# 6x24V_InjectorDrivers.net
KiCad netlist of a schematic drawn in Altium Designer
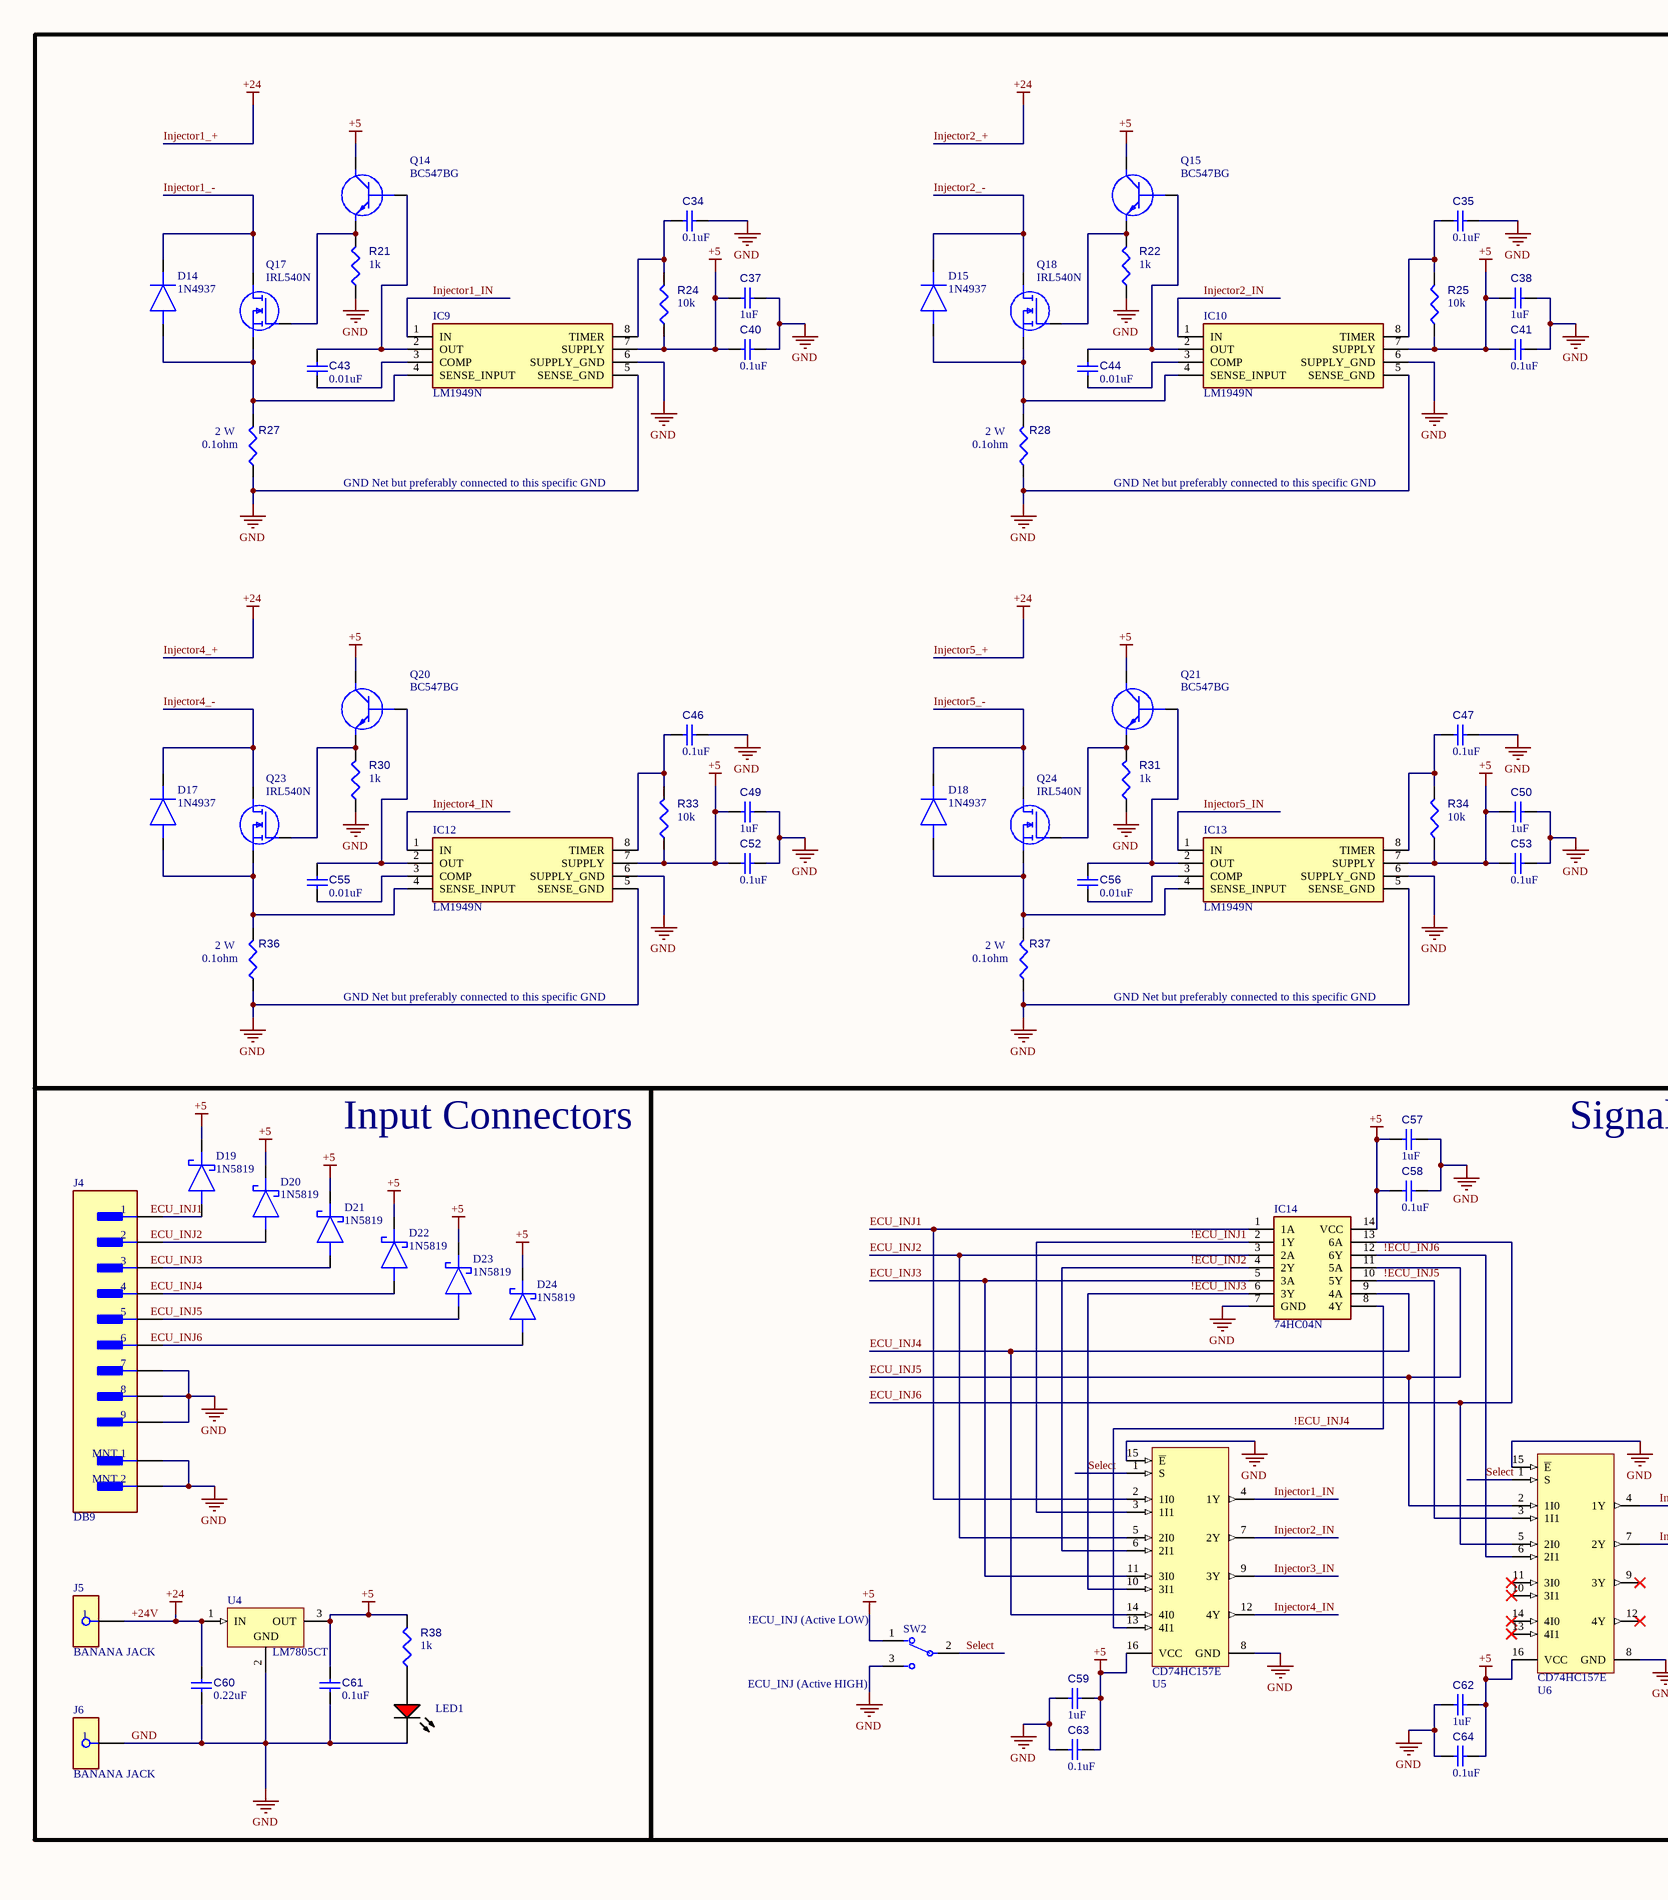
[diagram p0: 6x24V_InjectorDrivers.SchDoc, left]
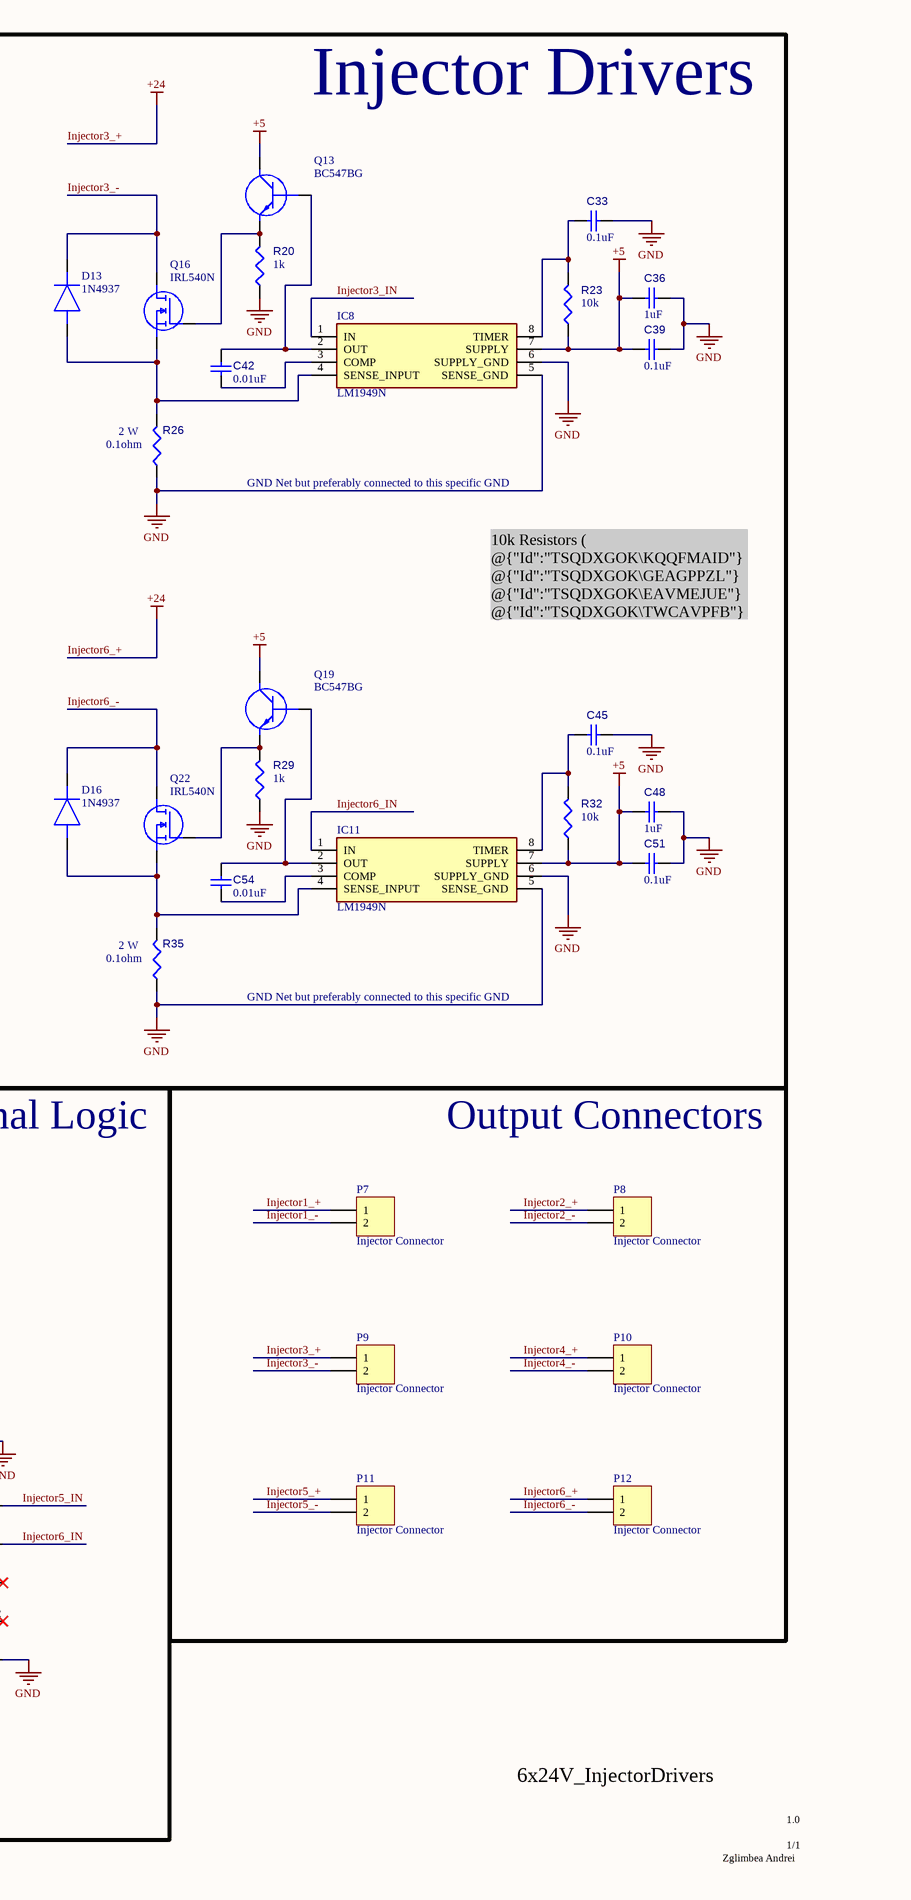
[diagram p1: 6x24V_InjectorDrivers.SchDoc, right]

(export (version "E")
  (design (tool "Eeschema 10.0.6"))
  (components
    (comp (ref "C33")
      (value "0.1uF")
      (footprint "CAPC0402(1005)60_L")
      (description "Chip Capacitor, 470nF +/-40%, 10V, 0402, Thickness 0.6 mm")
      (fields (field (name "TOLERANCE") "20%") (field (name "Comment") "100nF 12V"))
      (libsource (lib "Zglimbea Zglimbea") (part "CAP-NP-2"))
    )
    (comp (ref "C34")
      (value "0.1uF")
      (footprint "CAPC0402(1005)60_L")
      (description "Chip Capacitor, 470nF +/-40%, 10V, 0402, Thickness 0.6 mm")
      (fields (field (name "TOLERANCE") "20%") (field (name "Comment") "100nF 12V"))
      (libsource (lib "Zglimbea Zglimbea") (part "CAP-NP-2"))
    )
    (comp (ref "C35")
      (value "0.1uF")
      (footprint "CAPC0402(1005)60_L")
      (description "Chip Capacitor, 470nF +/-40%, 10V, 0402, Thickness 0.6 mm")
      (fields (field (name "TOLERANCE") "20%") (field (name "Comment") "100nF 12V"))
      (libsource (lib "Zglimbea Zglimbea") (part "CAP-NP-2"))
    )
    (comp (ref "C36")
      (value "1uF")
      (footprint "CAPC0402(1005)60_L")
      (description "Chip Capacitor, 470nF +/-40%, 10V, 0402, Thickness 0.6 mm")
      (fields (field (name "TOLERANCE") "20%") (field (name "Comment") "1uF 12V"))
      (libsource (lib "Zglimbea Zglimbea") (part "CAP-NP-2"))
    )
    (comp (ref "C37")
      (value "1uF")
      (footprint "CAPC0402(1005)60_L")
      (description "Chip Capacitor, 470nF +/-40%, 10V, 0402, Thickness 0.6 mm")
      (fields (field (name "TOLERANCE") "20%") (field (name "Comment") "1uF 12V"))
      (libsource (lib "Zglimbea Zglimbea") (part "CAP-NP-2"))
    )
    (comp (ref "C38")
      (value "1uF")
      (footprint "CAPC0402(1005)60_L")
      (description "Chip Capacitor, 470nF +/-40%, 10V, 0402, Thickness 0.6 mm")
      (fields (field (name "TOLERANCE") "20%") (field (name "Comment") "1uF 12V"))
      (libsource (lib "Zglimbea Zglimbea") (part "CAP-NP-2"))
    )
    (comp (ref "C39")
      (value "0.1uF")
      (footprint "CAPC0402(1005)60_L")
      (description "Chip Capacitor, 470nF +/-40%, 10V, 0402, Thickness 0.6 mm")
      (fields (field (name "TOLERANCE") "20%") (field (name "Comment") "100nF 12V"))
      (libsource (lib "Zglimbea Zglimbea") (part "CAP-NP-2"))
    )
    (comp (ref "C40")
      (value "0.1uF")
      (footprint "CAPC0402(1005)60_L")
      (description "Chip Capacitor, 470nF +/-40%, 10V, 0402, Thickness 0.6 mm")
      (fields (field (name "TOLERANCE") "20%") (field (name "Comment") "100nF 12V"))
      (libsource (lib "Zglimbea Zglimbea") (part "CAP-NP-2"))
    )
    (comp (ref "C41")
      (value "0.1uF")
      (footprint "CAPC0402(1005)60_L")
      (description "Chip Capacitor, 470nF +/-40%, 10V, 0402, Thickness 0.6 mm")
      (fields (field (name "TOLERANCE") "20%") (field (name "Comment") "100nF 12V"))
      (libsource (lib "Zglimbea Zglimbea") (part "CAP-NP-2"))
    )
    (comp (ref "C42")
      (value "0.01uF")
      (footprint "CAPC0402(1005)60_L")
      (description "Chip Capacitor, 470nF +/-40%, 10V, 0402, Thickness 0.6 mm")
      (fields (field (name "TOLERANCE") "20%") (field (name "Comment") "10nF 12V"))
      (libsource (lib "Zglimbea Zglimbea") (part "CAP-NP-2"))
    )
    (comp (ref "C43")
      (value "0.01uF")
      (footprint "CAPC0402(1005)60_L")
      (description "Chip Capacitor, 470nF +/-40%, 10V, 0402, Thickness 0.6 mm")
      (fields (field (name "TOLERANCE") "20%") (field (name "Comment") "10nF 12V"))
      (libsource (lib "Zglimbea Zglimbea") (part "CAP-NP-2"))
    )
    (comp (ref "C44")
      (value "0.01uF")
      (footprint "CAPC0402(1005)60_L")
      (description "Chip Capacitor, 470nF +/-40%, 10V, 0402, Thickness 0.6 mm")
      (fields (field (name "TOLERANCE") "20%") (field (name "Comment") "10nF 12V"))
      (libsource (lib "Zglimbea Zglimbea") (part "CAP-NP-2"))
    )
    (comp (ref "C45")
      (value "0.1uF")
      (footprint "CAPC0402(1005)60_L")
      (description "Chip Capacitor, 470nF +/-40%, 10V, 0402, Thickness 0.6 mm")
      (fields (field (name "TOLERANCE") "20%") (field (name "Comment") "100nF 12V"))
      (libsource (lib "Zglimbea Zglimbea") (part "CAP-NP-2"))
    )
    (comp (ref "C46")
      (value "0.1uF")
      (footprint "CAPC0402(1005)60_L")
      (description "Chip Capacitor, 470nF +/-40%, 10V, 0402, Thickness 0.6 mm")
      (fields (field (name "TOLERANCE") "20%") (field (name "Comment") "100nF 12V"))
      (libsource (lib "Zglimbea Zglimbea") (part "CAP-NP-2"))
    )
    (comp (ref "C47")
      (value "0.1uF")
      (footprint "CAPC0402(1005)60_L")
      (description "Chip Capacitor, 470nF +/-40%, 10V, 0402, Thickness 0.6 mm")
      (fields (field (name "TOLERANCE") "20%") (field (name "Comment") "100nF 12V"))
      (libsource (lib "Zglimbea Zglimbea") (part "CAP-NP-2"))
    )
    (comp (ref "C48")
      (value "1uF")
      (footprint "CAPC0402(1005)60_L")
      (description "Chip Capacitor, 470nF +/-40%, 10V, 0402, Thickness 0.6 mm")
      (fields (field (name "TOLERANCE") "20%") (field (name "Comment") "1uF 12V"))
      (libsource (lib "Zglimbea Zglimbea") (part "CAP-NP-2"))
    )
    (comp (ref "C49")
      (value "1uF")
      (footprint "CAPC0402(1005)60_L")
      (description "Chip Capacitor, 470nF +/-40%, 10V, 0402, Thickness 0.6 mm")
      (fields (field (name "TOLERANCE") "20%") (field (name "Comment") "1uF 12V"))
      (libsource (lib "Zglimbea Zglimbea") (part "CAP-NP-2"))
    )
    (comp (ref "C50")
      (value "1uF")
      (footprint "CAPC0402(1005)60_L")
      (description "Chip Capacitor, 470nF +/-40%, 10V, 0402, Thickness 0.6 mm")
      (fields (field (name "TOLERANCE") "20%") (field (name "Comment") "1uF 12V"))
      (libsource (lib "Zglimbea Zglimbea") (part "CAP-NP-2"))
    )
    (comp (ref "C51")
      (value "0.1uF")
      (footprint "CAPC0402(1005)60_L")
      (description "Chip Capacitor, 470nF +/-40%, 10V, 0402, Thickness 0.6 mm")
      (fields (field (name "TOLERANCE") "20%") (field (name "Comment") "100nF 12V"))
      (libsource (lib "Zglimbea Zglimbea") (part "CAP-NP-2"))
    )
    (comp (ref "C52")
      (value "0.1uF")
      (footprint "CAPC0402(1005)60_L")
      (description "Chip Capacitor, 470nF +/-40%, 10V, 0402, Thickness 0.6 mm")
      (fields (field (name "TOLERANCE") "20%") (field (name "Comment") "100nF 12V"))
      (libsource (lib "Zglimbea Zglimbea") (part "CAP-NP-2"))
    )
    (comp (ref "C53")
      (value "0.1uF")
      (footprint "CAPC0402(1005)60_L")
      (description "Chip Capacitor, 470nF +/-40%, 10V, 0402, Thickness 0.6 mm")
      (fields (field (name "TOLERANCE") "20%") (field (name "Comment") "100nF 12V"))
      (libsource (lib "Zglimbea Zglimbea") (part "CAP-NP-2"))
    )
    (comp (ref "C54")
      (value "0.01uF")
      (footprint "CAPC0402(1005)60_L")
      (description "Chip Capacitor, 470nF +/-40%, 10V, 0402, Thickness 0.6 mm")
      (fields (field (name "TOLERANCE") "20%") (field (name "Comment") "10nF 12V"))
      (libsource (lib "Zglimbea Zglimbea") (part "CAP-NP-2"))
    )
    (comp (ref "C55")
      (value "0.01uF")
      (footprint "CAPC0402(1005)60_L")
      (description "Chip Capacitor, 470nF +/-40%, 10V, 0402, Thickness 0.6 mm")
      (fields (field (name "TOLERANCE") "20%") (field (name "Comment") "10nF 12V"))
      (libsource (lib "Zglimbea Zglimbea") (part "CAP-NP-2"))
    )
    (comp (ref "C56")
      (value "0.01uF")
      (footprint "CAPC0402(1005)60_L")
      (description "Chip Capacitor, 470nF +/-40%, 10V, 0402, Thickness 0.6 mm")
      (fields (field (name "TOLERANCE") "20%") (field (name "Comment") "10nF 12V"))
      (libsource (lib "Zglimbea Zglimbea") (part "CAP-NP-2"))
    )
    (comp (ref "C57")
      (value "1uF")
      (footprint "CAPC0402(1005)60_L")
      (description "Chip Capacitor, 470nF +/-40%, 10V, 0402, Thickness 0.6 mm")
      (fields (field (name "TOLERANCE") "20%") (field (name "Comment") "1uF 12V"))
      (libsource (lib "Zglimbea Zglimbea") (part "CAP-NP-2"))
    )
    (comp (ref "C58")
      (value "0.1uF")
      (footprint "CAPC0402(1005)60_L")
      (description "Chip Capacitor, 470nF +/-40%, 10V, 0402, Thickness 0.6 mm")
      (fields (field (name "TOLERANCE") "20%") (field (name "Comment") "100nF 12V"))
      (libsource (lib "Zglimbea Zglimbea") (part "CAP-NP-2"))
    )
    (comp (ref "C59")
      (value "1uF")
      (footprint "CAPC0402(1005)60_L")
      (description "Chip Capacitor, 470nF +/-40%, 10V, 0402, Thickness 0.6 mm")
      (fields (field (name "TOLERANCE") "20%") (field (name "Comment") "1uF 12V"))
      (libsource (lib "Zglimbea Zglimbea") (part "CAP-NP-2"))
    )
    (comp (ref "C60")
      (value "0.22uF")
      (footprint "CAPC0402(1005)60_L")
      (description "Chip Capacitor, 470nF +/-40%, 10V, 0402, Thickness 0.6 mm")
      (fields (field (name "TOLERANCE") "20%") (field (name "Comment") "220nF 50V"))
      (libsource (lib "Zglimbea Zglimbea") (part "CAP-NP-2"))
    )
    (comp (ref "C61")
      (value "0.1uF")
      (footprint "CAPC0402(1005)60_L")
      (description "Chip Capacitor, 470nF +/-40%, 10V, 0402, Thickness 0.6 mm")
      (fields (field (name "TOLERANCE") "20%") (field (name "Comment") "100nF 50V"))
      (libsource (lib "Zglimbea Zglimbea") (part "CAP-NP-2"))
    )
    (comp (ref "C62")
      (value "1uF")
      (footprint "CAPC0402(1005)60_L")
      (description "Chip Capacitor, 470nF +/-40%, 10V, 0402, Thickness 0.6 mm")
      (fields (field (name "TOLERANCE") "20%") (field (name "Comment") "1uF 12V"))
      (libsource (lib "Zglimbea Zglimbea") (part "CAP-NP-2"))
    )
    (comp (ref "C63")
      (value "0.1uF")
      (footprint "CAPC0402(1005)60_L")
      (description "Chip Capacitor, 470nF +/-40%, 10V, 0402, Thickness 0.6 mm")
      (fields (field (name "TOLERANCE") "20%") (field (name "Comment") "100nF 12V"))
      (libsource (lib "Zglimbea Zglimbea") (part "CAP-NP-2"))
    )
    (comp (ref "C64")
      (value "0.1uF")
      (footprint "CAPC0402(1005)60_L")
      (description "Chip Capacitor, 470nF +/-40%, 10V, 0402, Thickness 0.6 mm")
      (fields (field (name "TOLERANCE") "20%") (field (name "Comment") "100nF 12V"))
      (libsource (lib "Zglimbea Zglimbea") (part "CAP-NP-2"))
    )
    (comp (ref "D13")
      (value "1N4937")
      (footprint "SamacSys:DIOAD1413W86L463D238")
      (description "Diode")
      (fields (field (name "MOUSER PART NUMBER") "863-1N4937"))
      (libsource (lib "*") (part "1N4937"))
    )
    (comp (ref "D14")
      (value "1N4937")
      (footprint "SamacSys:DIOAD1413W86L463D238")
      (description "Diode")
      (fields (field (name "MOUSER PART NUMBER") "863-1N4937"))
      (libsource (lib "*") (part "1N4937"))
    )
    (comp (ref "D15")
      (value "1N4937")
      (footprint "SamacSys:DIOAD1413W86L463D238")
      (description "Diode")
      (fields (field (name "MOUSER PART NUMBER") "863-1N4937"))
      (libsource (lib "*") (part "1N4937"))
    )
    (comp (ref "D16")
      (value "1N4937")
      (footprint "SamacSys:DIOAD1413W86L463D238")
      (description "Diode")
      (fields (field (name "MOUSER PART NUMBER") "863-1N4937"))
      (libsource (lib "*") (part "1N4937"))
    )
    (comp (ref "D17")
      (value "1N4937")
      (footprint "SamacSys:DIOAD1413W86L463D238")
      (description "Diode")
      (fields (field (name "MOUSER PART NUMBER") "863-1N4937"))
      (libsource (lib "*") (part "1N4937"))
    )
    (comp (ref "D18")
      (value "1N4937")
      (footprint "SamacSys:DIOAD1413W86L463D238")
      (description "Diode")
      (fields (field (name "MOUSER PART NUMBER") "863-1N4937"))
      (libsource (lib "*") (part "1N4937"))
    )
    (comp (ref "D19")
      (value "1N5819")
      (footprint "SamacSys:DIOAD1410W86L470D235")
      (description "Schottky Diode")
      (fields (field (name "MANUFACTURER_PART_NUMBER") "1N5819+"))
      (libsource (lib "*") (part "1N5819+"))
    )
    (comp (ref "D20")
      (value "1N5819")
      (footprint "SamacSys:DIOAD1410W86L470D235")
      (description "Schottky Diode")
      (fields (field (name "MANUFACTURER_PART_NUMBER") "1N5819+"))
      (libsource (lib "*") (part "1N5819+"))
    )
    (comp (ref "D21")
      (value "1N5819")
      (footprint "SamacSys:DIOAD1410W86L470D235")
      (description "Schottky Diode")
      (fields (field (name "MANUFACTURER_PART_NUMBER") "1N5819+"))
      (libsource (lib "*") (part "1N5819+"))
    )
    (comp (ref "D22")
      (value "1N5819")
      (footprint "SamacSys:DIOAD1410W86L470D235")
      (description "Schottky Diode")
      (fields (field (name "MANUFACTURER_PART_NUMBER") "1N5819+"))
      (libsource (lib "*") (part "1N5819+"))
    )
    (comp (ref "D23")
      (value "1N5819")
      (footprint "SamacSys:DIOAD1410W86L470D235")
      (description "Schottky Diode")
      (fields (field (name "MANUFACTURER_PART_NUMBER") "1N5819+"))
      (libsource (lib "*") (part "1N5819+"))
    )
    (comp (ref "D24")
      (value "1N5819")
      (footprint "SamacSys:DIOAD1410W86L470D235")
      (description "Schottky Diode")
      (fields (field (name "MANUFACTURER_PART_NUMBER") "1N5819+"))
      (libsource (lib "*") (part "1N5819+"))
    )
    (comp (ref "IC8")
      (value "LM1949N")
      (footprint "SamacSys:DIP794W53P254L959H508Q8N")
      (description "Integrated Circuit")
      (fields (field (name "MOUSER PART NUMBER") "926-LM1949N"))
      (libsource (lib "*") (part "LM1949N"))
    )
    (comp (ref "IC9")
      (value "LM1949N")
      (footprint "SamacSys:DIP794W53P254L959H508Q8N")
      (description "Integrated Circuit")
      (fields (field (name "MOUSER PART NUMBER") "926-LM1949N"))
      (libsource (lib "*") (part "LM1949N"))
    )
    (comp (ref "IC10")
      (value "LM1949N")
      (footprint "SamacSys:DIP794W53P254L959H508Q8N")
      (description "Integrated Circuit")
      (fields (field (name "MOUSER PART NUMBER") "926-LM1949N"))
      (libsource (lib "*") (part "LM1949N"))
    )
    (comp (ref "IC11")
      (value "LM1949N")
      (footprint "SamacSys:DIP794W53P254L959H508Q8N")
      (description "Integrated Circuit")
      (fields (field (name "MOUSER PART NUMBER") "926-LM1949N"))
      (libsource (lib "*") (part "LM1949N"))
    )
    (comp (ref "IC12")
      (value "LM1949N")
      (footprint "SamacSys:DIP794W53P254L959H508Q8N")
      (description "Integrated Circuit")
      (fields (field (name "MOUSER PART NUMBER") "926-LM1949N"))
      (libsource (lib "*") (part "LM1949N"))
    )
    (comp (ref "IC13")
      (value "LM1949N")
      (footprint "SamacSys:DIP794W53P254L959H508Q8N")
      (description "Integrated Circuit")
      (fields (field (name "MOUSER PART NUMBER") "926-LM1949N"))
      (libsource (lib "*") (part "LM1949N"))
    )
    (comp (ref "IC14")
      (value "74HC04N")
      (footprint "SamacSys:DIP762W53P254L1902H420Q14N")
      (description "Integrated Circuit")
      (libsource (lib "*") (part "74HC04N"))
    )
    (comp (ref "J4")
      (value "DB9")
      (footprint "FP-190-009-163R001-MFG")
      (description "190-009-163R001 D Type Connector, 9 Contact(s), Male, 0.109 inch Pitch, Solder Terminal, #4-40")
      (libsource (lib "Altium Content Vault") (part "bfa5909cba9379cb733595b161c4dbd"))
    )
    (comp (ref "J5")
      (value "BANANA JACK")
      (footprint "FP-1581-5-MFG")
      (description "CONN BANANA JACK TURRET GREEN")
      (libsource (lib "Altium Content Vault") (part "c5c826e0c4b67fe3b42ef77f2d4decc"))
    )
    (comp (ref "J6")
      (value "BANANA JACK")
      (footprint "FP-1581-5-MFG")
      (description "CONN BANANA JACK TURRET GREEN")
      (libsource (lib "Altium Content Vault") (part "c5c826e0c4b67fe3b42ef77f2d4decc"))
    )
    (comp (ref "LED1")
      (value "LED")
      (footprint "VISH-TLMX1100_V")
      (description "Red Led, 20mA, 2.1 V, -40 to 100 degC, 2-Pin SMD (0603), RoHS, Tape and Reel")
      (fields (field (name "MANUFACTURER") "Vishay Semiconductor") (field (name "POWER") "90mW"))
      (libsource (lib "Zglimbea Zglimbea") (part "LED-RED-AK-2"))
    )
    (comp (ref "P7")
      (value "Injector Connector")
      (footprint "HDR1X2")
      (description "Header, 2-Pin")
      (fields (field (name "PUBLISHER") "Altium Limited"))
      (libsource (lib "Miscellaneous Connectors") (part "Header 2"))
    )
    (comp (ref "P8")
      (value "Injector Connector")
      (footprint "HDR1X2")
      (description "Header, 2-Pin")
      (fields (field (name "PUBLISHER") "Altium Limited"))
      (libsource (lib "Miscellaneous Connectors") (part "Header 2"))
    )
    (comp (ref "P9")
      (value "Injector Connector")
      (footprint "HDR1X2")
      (description "Header, 2-Pin")
      (fields (field (name "PUBLISHER") "Altium Limited"))
      (libsource (lib "Miscellaneous Connectors") (part "Header 2"))
    )
    (comp (ref "P10")
      (value "Injector Connector")
      (footprint "HDR1X2")
      (description "Header, 2-Pin")
      (fields (field (name "PUBLISHER") "Altium Limited"))
      (libsource (lib "Miscellaneous Connectors") (part "Header 2"))
    )
    (comp (ref "P11")
      (value "Injector Connector")
      (footprint "HDR1X2")
      (description "Header, 2-Pin")
      (fields (field (name "PUBLISHER") "Altium Limited"))
      (libsource (lib "Miscellaneous Connectors") (part "Header 2"))
    )
    (comp (ref "P12")
      (value "Injector Connector")
      (footprint "HDR1X2")
      (description "Header, 2-Pin")
      (fields (field (name "PUBLISHER") "Altium Limited"))
      (libsource (lib "Miscellaneous Connectors") (part "Header 2"))
    )
    (comp (ref "Q13")
      (value "BC547BG")
      (footprint "SamacSys:BC547BG")
      (description "Transistor BJT NPN")
      (libsource (lib "*") (part "BC547BG"))
    )
    (comp (ref "Q14")
      (value "BC547BG")
      (footprint "SamacSys:BC547BG")
      (description "Transistor BJT NPN")
      (libsource (lib "*") (part "BC547BG"))
    )
    (comp (ref "Q15")
      (value "BC547BG")
      (footprint "SamacSys:BC547BG")
      (description "Transistor BJT NPN")
      (libsource (lib "*") (part "BC547BG"))
    )
    (comp (ref "Q16")
      (value "IRL540N")
      (footprint "SamacSys:TO254P469X1042X1967-3P")
      (description "MOSFET (N-Channel)")
      (libsource (lib "*") (part "IRL540N"))
    )
    (comp (ref "Q17")
      (value "IRL540N")
      (footprint "SamacSys:TO254P469X1042X1967-3P")
      (description "MOSFET (N-Channel)")
      (libsource (lib "*") (part "IRL540N"))
    )
    (comp (ref "Q18")
      (value "IRL540N")
      (footprint "SamacSys:TO254P469X1042X1967-3P")
      (description "MOSFET (N-Channel)")
      (libsource (lib "*") (part "IRL540N"))
    )
    (comp (ref "Q19")
      (value "BC547BG")
      (footprint "SamacSys:BC547BG")
      (description "Transistor BJT NPN")
      (libsource (lib "*") (part "BC547BG"))
    )
    (comp (ref "Q20")
      (value "BC547BG")
      (footprint "SamacSys:BC547BG")
      (description "Transistor BJT NPN")
      (libsource (lib "*") (part "BC547BG"))
    )
    (comp (ref "Q21")
      (value "BC547BG")
      (footprint "SamacSys:BC547BG")
      (description "Transistor BJT NPN")
      (libsource (lib "*") (part "BC547BG"))
    )
    (comp (ref "Q22")
      (value "IRL540N")
      (footprint "SamacSys:TO254P469X1042X1967-3P")
      (description "MOSFET (N-Channel)")
      (libsource (lib "*") (part "IRL540N"))
    )
    (comp (ref "Q23")
      (value "IRL540N")
      (footprint "SamacSys:TO254P469X1042X1967-3P")
      (description "MOSFET (N-Channel)")
      (libsource (lib "*") (part "IRL540N"))
    )
    (comp (ref "Q24")
      (value "IRL540N")
      (footprint "SamacSys:TO254P469X1042X1967-3P")
      (description "MOSFET (N-Channel)")
      (libsource (lib "*") (part "IRL540N"))
    )
    (comp (ref "R20")
      (value "1k")
      (footprint "RESC0402(1005)_L")
      (description "Chip Resistor, 240 Ohms, +/-5 %, 63 mW, -55 to 155 degC, 0402")
      (fields (field (name "TOLERANCE") "5%") (field (name "Comment") "1k 0.5W"))
      (libsource (lib "Zglimbea Zglimbea") (part "RES-2"))
    )
    (comp (ref "R21")
      (value "1k")
      (footprint "RESC0402(1005)_L")
      (description "Chip Resistor, 240 Ohms, +/-5 %, 63 mW, -55 to 155 degC, 0402")
      (fields (field (name "TOLERANCE") "5%") (field (name "Comment") "1k 0.5W"))
      (libsource (lib "Zglimbea Zglimbea") (part "RES-2"))
    )
    (comp (ref "R22")
      (value "1k")
      (footprint "RESC0402(1005)_L")
      (description "Chip Resistor, 240 Ohms, +/-5 %, 63 mW, -55 to 155 degC, 0402")
      (fields (field (name "TOLERANCE") "5%") (field (name "Comment") "1k 0.5W"))
      (libsource (lib "Zglimbea Zglimbea") (part "RES-2"))
    )
    (comp (ref "R23")
      (value "10k")
      (footprint "RESC0402(1005)_L")
      (description "Chip Resistor, 240 Ohms, +/-5 %, 63 mW, -55 to 155 degC, 0402")
      (fields (field (name "TOLERANCE") "5%") (field (name "Comment") "10k 0.5W"))
      (libsource (lib "Zglimbea Zglimbea") (part "RES-2"))
    )
    (comp (ref "R24")
      (value "10k")
      (footprint "RESC0402(1005)_L")
      (description "Chip Resistor, 240 Ohms, +/-5 %, 63 mW, -55 to 155 degC, 0402")
      (fields (field (name "TOLERANCE") "5%") (field (name "Comment") "10k 0.5W"))
      (libsource (lib "Zglimbea Zglimbea") (part "RES-2"))
    )
    (comp (ref "R25")
      (value "10k")
      (footprint "RESC0402(1005)_L")
      (description "Chip Resistor, 240 Ohms, +/-5 %, 63 mW, -55 to 155 degC, 0402")
      (fields (field (name "TOLERANCE") "5%") (field (name "Comment") "10k 0.5W"))
      (libsource (lib "Zglimbea Zglimbea") (part "RES-2"))
    )
    (comp (ref "R26")
      (value "0.1ohm")
      (footprint "RESC0402(1005)_L")
      (description "Chip Resistor, 240 Ohms, +/-5 %, 63 mW, -55 to 155 degC, 0402")
      (fields
        (field (name "POWER") "2 W")
        (field (name "TOLERANCE") "5%")
        (field (name "Comment") "0.1Ohm 2W")
      )
      (libsource (lib "Zglimbea Zglimbea") (part "RES-2"))
    )
    (comp (ref "R27")
      (value "0.1ohm")
      (footprint "RESC0402(1005)_L")
      (description "0.1 Ohm 1% 0.5W")
      (fields
        (field (name "POWER") "2 W")
        (field (name "TOLERANCE") "5%")
        (field (name "Comment") "0.1Ohm 2W")
      )
      (libsource (lib "Zglimbea Zglimbea") (part "RES-2"))
    )
    (comp (ref "R28")
      (value "0.1ohm")
      (footprint "RESC0402(1005)_L")
      (description "0.1 Ohm 1% 0.5W")
      (fields
        (field (name "POWER") "2 W")
        (field (name "TOLERANCE") "5%")
        (field (name "Comment") "0.1Ohm 2W")
      )
      (libsource (lib "Zglimbea Zglimbea") (part "RES-2"))
    )
    (comp (ref "R29")
      (value "1k")
      (footprint "RESC0402(1005)_L")
      (description "Chip Resistor, 240 Ohms, +/-5 %, 63 mW, -55 to 155 degC, 0402")
      (fields (field (name "TOLERANCE") "5%") (field (name "Comment") "1k 0.5W"))
      (libsource (lib "Zglimbea Zglimbea") (part "RES-2"))
    )
    (comp (ref "R30")
      (value "1k")
      (footprint "RESC0402(1005)_L")
      (description "Chip Resistor, 240 Ohms, +/-5 %, 63 mW, -55 to 155 degC, 0402")
      (fields (field (name "TOLERANCE") "5%") (field (name "Comment") "1k 0.5W"))
      (libsource (lib "Zglimbea Zglimbea") (part "RES-2"))
    )
    (comp (ref "R31")
      (value "1k")
      (footprint "RESC0402(1005)_L")
      (description "Chip Resistor, 240 Ohms, +/-5 %, 63 mW, -55 to 155 degC, 0402")
      (fields (field (name "TOLERANCE") "5%") (field (name "Comment") "1k 0.5W"))
      (libsource (lib "Zglimbea Zglimbea") (part "RES-2"))
    )
    (comp (ref "R32")
      (value "10k")
      (footprint "RESC0402(1005)_L")
      (description "Chip Resistor, 240 Ohms, +/-5 %, 63 mW, -55 to 155 degC, 0402")
      (fields (field (name "TOLERANCE") "5%") (field (name "Comment") "10k 0.5W"))
      (libsource (lib "Zglimbea Zglimbea") (part "RES-2"))
    )
    (comp (ref "R33")
      (value "10k")
      (footprint "RESC0402(1005)_L")
      (description "Chip Resistor, 240 Ohms, +/-5 %, 63 mW, -55 to 155 degC, 0402")
      (fields (field (name "TOLERANCE") "5%") (field (name "Comment") "10k 0.5W"))
      (libsource (lib "Zglimbea Zglimbea") (part "RES-2"))
    )
    (comp (ref "R34")
      (value "10k")
      (footprint "RESC0402(1005)_L")
      (description "Chip Resistor, 240 Ohms, +/-5 %, 63 mW, -55 to 155 degC, 0402")
      (fields (field (name "TOLERANCE") "5%") (field (name "Comment") "10k 0.5W"))
      (libsource (lib "Zglimbea Zglimbea") (part "RES-2"))
    )
    (comp (ref "R35")
      (value "0.1ohm")
      (footprint "RESC0402(1005)_L")
      (description "Chip Resistor, 240 Ohms, +/-5 %, 63 mW, -55 to 155 degC, 0402")
      (fields
        (field (name "POWER") "2 W")
        (field (name "TOLERANCE") "5%")
        (field (name "Comment") "0.1Ohm 2W")
      )
      (libsource (lib "Zglimbea Zglimbea") (part "RES-2"))
    )
    (comp (ref "R36")
      (value "0.1ohm")
      (footprint "RESC0402(1005)_L")
      (description "0.1 Ohm 1% 0.5W")
      (fields
        (field (name "POWER") "2 W")
        (field (name "TOLERANCE") "5%")
        (field (name "Comment") "0.1Ohm 2W")
      )
      (libsource (lib "Zglimbea Zglimbea") (part "RES-2"))
    )
    (comp (ref "R37")
      (value "0.1ohm")
      (footprint "RESC0402(1005)_L")
      (description "0.1 Ohm 1% 0.5W")
      (fields
        (field (name "POWER") "2 W")
        (field (name "TOLERANCE") "5%")
        (field (name "Comment") "0.1Ohm 2W")
      )
      (libsource (lib "Zglimbea Zglimbea") (part "RES-2"))
    )
    (comp (ref "R38")
      (value "1k")
      (footprint "RESC0402(1005)_L")
      (description "Chip Resistor, 240 Ohms, +/-5 %, 63 mW, -55 to 155 degC, 0402")
      (fields (field (name "TOLERANCE") "5%") (field (name "Comment") "1k 0.5W"))
      (libsource (lib "Zglimbea Zglimbea") (part "RES-2"))
    )
    (comp (ref "SW2")
      (value "SPDT SW")
      (footprint "FP-A101SYCB04-MFG")
      (description "SWITCH TOGGLE SPDT 0.4VA 20V")
      (libsource (lib "Altium Content Vault") (part "52c419afdc2a387c7d548259a9aeefb"))
    )
    (comp (ref "U4")
      (value "LM7805CT")
      (footprint "FAIR-TO-220-3")
      (description "Positive Voltage Regulator, 5 V, 1 A, -40 to 125 degC, 3-Pin TO-220, RoHS, Tube")
      (fields (field (name "MANUFACTURER") "FairchildSemiconductor"))
      (libsource (lib "Altium Content Vault") (part "FAIR-LM7805CT-TO220-3"))
    )
    (comp (ref "U5")
      (value "CD74HC157E")
      (footprint "N0016A")
      (description "High Speed CMOS Logic Quad 2-Input Multiplexers, N0016A, TUBE")
      (fields
        (field (name "GENERIC PART NUMBER") "CD74HC157")
        (field (name "MANUFACTURER") "Texas Instruments")
      )
      (libsource (lib "Altium Content Vault") (part "TI-CD54_74HCX157-16"))
    )
    (comp (ref "U6")
      (value "CD74HC157E")
      (footprint "N0016A")
      (description "High Speed CMOS Logic Quad 2-Input Multiplexers, N0016A, TUBE")
      (fields
        (field (name "GENERIC PART NUMBER") "CD74HC157")
        (field (name "MANUFACTURER") "Texas Instruments")
      )
      (libsource (lib "Altium Content Vault") (part "TI-CD54_74HCX157-16"))
    )
  )
  (nets
    (net (code "1") (name "+5") (class "Default")
      (node (ref "C36") (pin "1") (pinfunction "1_1") (pintype "passive"))
      (node (ref "C37") (pin "1") (pinfunction "1_1") (pintype "passive"))
      (node (ref "C38") (pin "1") (pinfunction "1_1") (pintype "passive"))
      (node (ref "C39") (pin "1") (pinfunction "1_1") (pintype "passive"))
      (node (ref "C40") (pin "1") (pinfunction "1_1") (pintype "passive"))
      (node (ref "C41") (pin "1") (pinfunction "1_1") (pintype "passive"))
      (node (ref "C48") (pin "1") (pinfunction "1_1") (pintype "passive"))
      (node (ref "C49") (pin "1") (pinfunction "1_1") (pintype "passive"))
      (node (ref "C50") (pin "1") (pinfunction "1_1") (pintype "passive"))
      (node (ref "C51") (pin "1") (pinfunction "1_1") (pintype "passive"))
      (node (ref "C52") (pin "1") (pinfunction "1_1") (pintype "passive"))
      (node (ref "C53") (pin "1") (pinfunction "1_1") (pintype "passive"))
      (node (ref "C57") (pin "1") (pinfunction "1_1") (pintype "passive"))
      (node (ref "C58") (pin "1") (pinfunction "1_1") (pintype "passive"))
      (node (ref "C59") (pin "2") (pinfunction "2_2") (pintype "passive"))
      (node (ref "C61") (pin "1") (pinfunction "1_1") (pintype "passive"))
      (node (ref "C62") (pin "2") (pinfunction "2_2") (pintype "passive"))
      (node (ref "C63") (pin "2") (pinfunction "2_2") (pintype "passive"))
      (node (ref "C64") (pin "2") (pinfunction "2_2") (pintype "passive"))
      (node (ref "D19") (pin "1") (pinfunction "K_1") (pintype "passive"))
      (node (ref "D20") (pin "1") (pinfunction "K_1") (pintype "passive"))
      (node (ref "D21") (pin "1") (pinfunction "K_1") (pintype "passive"))
      (node (ref "D22") (pin "1") (pinfunction "K_1") (pintype "passive"))
      (node (ref "D23") (pin "1") (pinfunction "K_1") (pintype "passive"))
      (node (ref "D24") (pin "1") (pinfunction "K_1") (pintype "passive"))
      (node (ref "IC10") (pin "7") (pinfunction "SUPPLY_7") (pintype "passive"))
      (node (ref "IC11") (pin "7") (pinfunction "SUPPLY_7") (pintype "passive"))
      (node (ref "IC12") (pin "7") (pinfunction "SUPPLY_7") (pintype "passive"))
      (node (ref "IC13") (pin "7") (pinfunction "SUPPLY_7") (pintype "passive"))
      (node (ref "IC14") (pin "14") (pinfunction "VCC_14") (pintype "power_in"))
      (node (ref "IC8") (pin "7") (pinfunction "SUPPLY_7") (pintype "passive"))
      (node (ref "IC9") (pin "7") (pinfunction "SUPPLY_7") (pintype "passive"))
      (node (ref "Q13") (pin "1") (pinfunction "C_1") (pintype "passive"))
      (node (ref "Q14") (pin "1") (pinfunction "C_1") (pintype "passive"))
      (node (ref "Q15") (pin "1") (pinfunction "C_1") (pintype "passive"))
      (node (ref "Q19") (pin "1") (pinfunction "C_1") (pintype "passive"))
      (node (ref "Q20") (pin "1") (pinfunction "C_1") (pintype "passive"))
      (node (ref "Q21") (pin "1") (pinfunction "C_1") (pintype "passive"))
      (node (ref "R23") (pin "1") (pinfunction "1_1") (pintype "passive"))
      (node (ref "R24") (pin "1") (pinfunction "1_1") (pintype "passive"))
      (node (ref "R25") (pin "1") (pinfunction "1_1") (pintype "passive"))
      (node (ref "R32") (pin "1") (pinfunction "1_1") (pintype "passive"))
      (node (ref "R33") (pin "1") (pinfunction "1_1") (pintype "passive"))
      (node (ref "R34") (pin "1") (pinfunction "1_1") (pintype "passive"))
      (node (ref "R38") (pin "2") (pinfunction "2_2") (pintype "passive"))
      (node (ref "SW2") (pin "1") (pinfunction "1_1") (pintype "passive"))
      (node (ref "U4") (pin "3") (pinfunction "OUT_3") (pintype "power_in"))
      (node (ref "U5") (pin "16") (pinfunction "VCC_16") (pintype "power_in"))
      (node (ref "U6") (pin "16") (pinfunction "VCC_16") (pintype "power_in"))
    )
    (net (code "2") (name "+24") (class "Default")
      (node (ref "C60") (pin "1") (pinfunction "1_1") (pintype "passive"))
      (node (ref "J5") (pin "1") (pinfunction "1_1") (pintype "passive"))
      (node (ref "P10") (pin "1") (pinfunction "1_1") (pintype "passive"))
      (node (ref "P11") (pin "1") (pinfunction "1_1") (pintype "passive"))
      (node (ref "P12") (pin "1") (pinfunction "1_1") (pintype "passive"))
      (node (ref "P7") (pin "1") (pinfunction "1_1") (pintype "passive"))
      (node (ref "P8") (pin "1") (pinfunction "1_1") (pintype "passive"))
      (node (ref "P9") (pin "1") (pinfunction "1_1") (pintype "passive"))
      (node (ref "U4") (pin "1") (pinfunction "IN_1") (pintype "input"))
    )
    (net (code "3") (name "/!ECU_INJ1") (class "Default")
      (node (ref "IC14") (pin "2") (pinfunction "1Y_2") (pintype "passive"))
      (node (ref "U5") (pin "3") (pinfunction "1I1_3") (pintype "input"))
    )
    (net (code "4") (name "/!ECU_INJ2") (class "Default")
      (node (ref "IC14") (pin "4") (pinfunction "2Y_4") (pintype "passive"))
      (node (ref "U5") (pin "6") (pinfunction "2I1_6") (pintype "input"))
    )
    (net (code "5") (name "/!ECU_INJ3") (class "Default")
      (node (ref "IC14") (pin "12") (pinfunction "6Y_12") (pintype "passive"))
      (node (ref "IC14") (pin "6") (pinfunction "3Y_6") (pintype "passive"))
      (node (ref "SW2") (pin "2") (pinfunction "2_2") (pintype "passive"))
      (node (ref "U5") (pin "1") (pinfunction "S_1") (pintype "input"))
      (node (ref "U5") (pin "10") (pinfunction "3I1_10") (pintype "input"))
      (node (ref "U6") (pin "1") (pinfunction "S_1") (pintype "input"))
      (node (ref "U6") (pin "6") (pinfunction "2I1_6") (pintype "input"))
    )
    (net (code "6") (name "/!ECU_INJ4") (class "Default")
      (node (ref "IC14") (pin "8") (pinfunction "4Y_8") (pintype "passive"))
      (node (ref "U5") (pin "13") (pinfunction "4I1_13") (pintype "input"))
    )
    (net (code "7") (name "/!ECU_INJ5") (class "Default")
      (node (ref "IC14") (pin "10") (pinfunction "5Y_10") (pintype "passive"))
      (node (ref "U6") (pin "3") (pinfunction "1I1_3") (pintype "input"))
    )
    (net (code "8") (name "/ECU_INJ1") (class "Default")
      (node (ref "IC14") (pin "1") (pinfunction "1A_1") (pintype "passive"))
      (node (ref "U5") (pin "2") (pinfunction "1I0_2") (pintype "input"))
    )
    (net (code "9") (name "/ECU_INJ2") (class "Default")
      (node (ref "IC14") (pin "3") (pinfunction "2A_3") (pintype "passive"))
      (node (ref "U5") (pin "5") (pinfunction "2I0_5") (pintype "input"))
    )
    (net (code "10") (name "/ECU_INJ3") (class "Default")
      (node (ref "IC14") (pin "5") (pinfunction "3A_5") (pintype "passive"))
      (node (ref "U5") (pin "11") (pinfunction "3I0_11") (pintype "input"))
    )
    (net (code "11") (name "/ECU_INJ4") (class "Default")
      (node (ref "IC14") (pin "9") (pinfunction "4A_9") (pintype "passive"))
      (node (ref "U5") (pin "14") (pinfunction "4I0_14") (pintype "input"))
    )
    (net (code "12") (name "/ECU_INJ5") (class "Default")
      (node (ref "IC14") (pin "11") (pinfunction "5A_11") (pintype "passive"))
      (node (ref "U6") (pin "2") (pinfunction "1I0_2") (pintype "input"))
    )
    (net (code "13") (name "/ECU_INJ6") (class "Default")
      (node (ref "IC14") (pin "13") (pinfunction "6A_13") (pintype "passive"))
      (node (ref "U6") (pin "5") (pinfunction "2I0_5") (pintype "input"))
    )
    (net (code "14") (name "/Injector1_-") (class "Default")
      (node (ref "D14") (pin "1") (pinfunction "K_1") (pintype "passive"))
      (node (ref "P7") (pin "2") (pinfunction "2_2") (pintype "passive"))
      (node (ref "Q17") (pin "2") (pinfunction "D_2") (pintype "passive"))
    )
    (net (code "15") (name "/Injector1_IN") (class "Default")
      (node (ref "IC9") (pin "1") (pinfunction "IN_1") (pintype "passive"))
      (node (ref "U5") (pin "4") (pinfunction "1Y_4") (pintype "output"))
    )
    (net (code "16") (name "/Injector2_-") (class "Default")
      (node (ref "D15") (pin "1") (pinfunction "K_1") (pintype "passive"))
      (node (ref "P8") (pin "2") (pinfunction "2_2") (pintype "passive"))
      (node (ref "Q18") (pin "2") (pinfunction "D_2") (pintype "passive"))
    )
    (net (code "17") (name "/Injector2_IN") (class "Default")
      (node (ref "IC10") (pin "1") (pinfunction "IN_1") (pintype "passive"))
      (node (ref "U5") (pin "7") (pinfunction "2Y_7") (pintype "output"))
    )
    (net (code "18") (name "/Injector3_-") (class "Default")
      (node (ref "D13") (pin "1") (pinfunction "K_1") (pintype "passive"))
      (node (ref "P9") (pin "2") (pinfunction "2_2") (pintype "passive"))
      (node (ref "Q16") (pin "2") (pinfunction "D_2") (pintype "passive"))
    )
    (net (code "19") (name "/Injector3_IN") (class "Default")
      (node (ref "IC8") (pin "1") (pinfunction "IN_1") (pintype "passive"))
      (node (ref "U5") (pin "9") (pinfunction "3Y_9") (pintype "output"))
    )
    (net (code "20") (name "/Injector4_-") (class "Default")
      (node (ref "D17") (pin "1") (pinfunction "K_1") (pintype "passive"))
      (node (ref "P10") (pin "2") (pinfunction "2_2") (pintype "passive"))
      (node (ref "Q23") (pin "2") (pinfunction "D_2") (pintype "passive"))
    )
    (net (code "21") (name "/Injector4_IN") (class "Default")
      (node (ref "IC12") (pin "1") (pinfunction "IN_1") (pintype "passive"))
      (node (ref "U5") (pin "12") (pinfunction "4Y_12") (pintype "output"))
    )
    (net (code "22") (name "/Injector5_-") (class "Default")
      (node (ref "D18") (pin "1") (pinfunction "K_1") (pintype "passive"))
      (node (ref "P11") (pin "2") (pinfunction "2_2") (pintype "passive"))
      (node (ref "Q24") (pin "2") (pinfunction "D_2") (pintype "passive"))
    )
    (net (code "23") (name "/Injector5_IN") (class "Default")
      (node (ref "IC13") (pin "1") (pinfunction "IN_1") (pintype "passive"))
      (node (ref "U6") (pin "4") (pinfunction "1Y_4") (pintype "output"))
    )
    (net (code "24") (name "/Injector6_-") (class "Default")
      (node (ref "D16") (pin "1") (pinfunction "K_1") (pintype "passive"))
      (node (ref "P12") (pin "2") (pinfunction "2_2") (pintype "passive"))
      (node (ref "Q22") (pin "2") (pinfunction "D_2") (pintype "passive"))
    )
    (net (code "25") (name "/Injector6_IN") (class "Default")
      (node (ref "IC11") (pin "1") (pinfunction "IN_1") (pintype "passive"))
      (node (ref "U6") (pin "7") (pinfunction "2Y_7") (pintype "output"))
    )
    (net (code "26") (name "GND") (class "Default")
      (node (ref "C33") (pin "2") (pinfunction "2_2") (pintype "passive"))
      (node (ref "C34") (pin "2") (pinfunction "2_2") (pintype "passive"))
      (node (ref "C35") (pin "2") (pinfunction "2_2") (pintype "passive"))
      (node (ref "C36") (pin "2") (pinfunction "2_2") (pintype "passive"))
      (node (ref "C37") (pin "2") (pinfunction "2_2") (pintype "passive"))
      (node (ref "C38") (pin "2") (pinfunction "2_2") (pintype "passive"))
      (node (ref "C39") (pin "2") (pinfunction "2_2") (pintype "passive"))
      (node (ref "C40") (pin "2") (pinfunction "2_2") (pintype "passive"))
      (node (ref "C41") (pin "2") (pinfunction "2_2") (pintype "passive"))
      (node (ref "C45") (pin "2") (pinfunction "2_2") (pintype "passive"))
      (node (ref "C46") (pin "2") (pinfunction "2_2") (pintype "passive"))
      (node (ref "C47") (pin "2") (pinfunction "2_2") (pintype "passive"))
      (node (ref "C48") (pin "2") (pinfunction "2_2") (pintype "passive"))
      (node (ref "C49") (pin "2") (pinfunction "2_2") (pintype "passive"))
      (node (ref "C50") (pin "2") (pinfunction "2_2") (pintype "passive"))
      (node (ref "C51") (pin "2") (pinfunction "2_2") (pintype "passive"))
      (node (ref "C52") (pin "2") (pinfunction "2_2") (pintype "passive"))
      (node (ref "C53") (pin "2") (pinfunction "2_2") (pintype "passive"))
      (node (ref "C57") (pin "2") (pinfunction "2_2") (pintype "passive"))
      (node (ref "C58") (pin "2") (pinfunction "2_2") (pintype "passive"))
      (node (ref "C59") (pin "1") (pinfunction "1_1") (pintype "passive"))
      (node (ref "C60") (pin "2") (pinfunction "2_2") (pintype "passive"))
      (node (ref "C61") (pin "2") (pinfunction "2_2") (pintype "passive"))
      (node (ref "C62") (pin "1") (pinfunction "1_1") (pintype "passive"))
      (node (ref "C63") (pin "1") (pinfunction "1_1") (pintype "passive"))
      (node (ref "C64") (pin "1") (pinfunction "1_1") (pintype "passive"))
      (node (ref "IC10") (pin "5") (pinfunction "SENSE_GND_5") (pintype "passive"))
      (node (ref "IC10") (pin "6") (pinfunction "SUPPLY_GND_6") (pintype "passive"))
      (node (ref "IC11") (pin "5") (pinfunction "SENSE_GND_5") (pintype "passive"))
      (node (ref "IC11") (pin "6") (pinfunction "SUPPLY_GND_6") (pintype "passive"))
      (node (ref "IC12") (pin "5") (pinfunction "SENSE_GND_5") (pintype "passive"))
      (node (ref "IC12") (pin "6") (pinfunction "SUPPLY_GND_6") (pintype "passive"))
      (node (ref "IC13") (pin "5") (pinfunction "SENSE_GND_5") (pintype "passive"))
      (node (ref "IC13") (pin "6") (pinfunction "SUPPLY_GND_6") (pintype "passive"))
      (node (ref "IC14") (pin "7") (pinfunction "GND_7") (pintype "power_in"))
      (node (ref "IC8") (pin "5") (pinfunction "SENSE_GND_5") (pintype "passive"))
      (node (ref "IC8") (pin "6") (pinfunction "SUPPLY_GND_6") (pintype "passive"))
      (node (ref "IC9") (pin "5") (pinfunction "SENSE_GND_5") (pintype "passive"))
      (node (ref "IC9") (pin "6") (pinfunction "SUPPLY_GND_6") (pintype "passive"))
      (node (ref "J4") (pin "10") (pinfunction "MNT_1_10") (pintype "passive"))
      (node (ref "J4") (pin "11") (pinfunction "MNT_2_11") (pintype "passive"))
      (node (ref "J4") (pin "7") (pinfunction "7_7") (pintype "passive"))
      (node (ref "J4") (pin "8") (pinfunction "8_8") (pintype "passive"))
      (node (ref "J4") (pin "9") (pinfunction "9_9") (pintype "passive"))
      (node (ref "J6") (pin "1") (pinfunction "1_1") (pintype "passive"))
      (node (ref "LED1") (pin "2") (pinfunction "K_2") (pintype "passive"))
      (node (ref "R20") (pin "1") (pinfunction "1_1") (pintype "passive"))
      (node (ref "R21") (pin "1") (pinfunction "1_1") (pintype "passive"))
      (node (ref "R22") (pin "1") (pinfunction "1_1") (pintype "passive"))
      (node (ref "R26") (pin "1") (pinfunction "1_1") (pintype "passive"))
      (node (ref "R27") (pin "1") (pinfunction "1_1") (pintype "passive"))
      (node (ref "R28") (pin "1") (pinfunction "1_1") (pintype "passive"))
      (node (ref "R29") (pin "1") (pinfunction "1_1") (pintype "passive"))
      (node (ref "R30") (pin "1") (pinfunction "1_1") (pintype "passive"))
      (node (ref "R31") (pin "1") (pinfunction "1_1") (pintype "passive"))
      (node (ref "R35") (pin "1") (pinfunction "1_1") (pintype "passive"))
      (node (ref "R36") (pin "1") (pinfunction "1_1") (pintype "passive"))
      (node (ref "R37") (pin "1") (pinfunction "1_1") (pintype "passive"))
      (node (ref "SW2") (pin "3") (pinfunction "3_3") (pintype "passive"))
      (node (ref "U4") (pin "2") (pinfunction "GND_2") (pintype "power_in"))
      (node (ref "U5") (pin "15") (pinfunction "~{E}_15") (pintype "input"))
      (node (ref "U5") (pin "8") (pinfunction "GND_8") (pintype "power_in"))
      (node (ref "U6") (pin "15") (pinfunction "~{E}_15") (pintype "input"))
      (node (ref "U6") (pin "8") (pinfunction "GND_8") (pintype "power_in"))
    )
    (net (code "27") (name "Net-(D13-A)") (class "Default")
      (node (ref "D13") (pin "2") (pinfunction "A_2") (pintype "passive"))
      (node (ref "IC8") (pin "4") (pinfunction "SENSE_INPUT_4") (pintype "passive"))
      (node (ref "Q16") (pin "3") (pinfunction "S_3") (pintype "passive"))
      (node (ref "R26") (pin "2") (pinfunction "2_2") (pintype "passive"))
    )
    (net (code "28") (name "Net-(D14-A)") (class "Default")
      (node (ref "D14") (pin "2") (pinfunction "A_2") (pintype "passive"))
      (node (ref "IC9") (pin "4") (pinfunction "SENSE_INPUT_4") (pintype "passive"))
      (node (ref "Q17") (pin "3") (pinfunction "S_3") (pintype "passive"))
      (node (ref "R27") (pin "2") (pinfunction "2_2") (pintype "passive"))
    )
    (net (code "29") (name "Net-(D15-A)") (class "Default")
      (node (ref "D15") (pin "2") (pinfunction "A_2") (pintype "passive"))
      (node (ref "IC10") (pin "4") (pinfunction "SENSE_INPUT_4") (pintype "passive"))
      (node (ref "Q18") (pin "3") (pinfunction "S_3") (pintype "passive"))
      (node (ref "R28") (pin "2") (pinfunction "2_2") (pintype "passive"))
    )
    (net (code "30") (name "Net-(D16-A)") (class "Default")
      (node (ref "D16") (pin "2") (pinfunction "A_2") (pintype "passive"))
      (node (ref "IC11") (pin "4") (pinfunction "SENSE_INPUT_4") (pintype "passive"))
      (node (ref "Q22") (pin "3") (pinfunction "S_3") (pintype "passive"))
      (node (ref "R35") (pin "2") (pinfunction "2_2") (pintype "passive"))
    )
    (net (code "31") (name "Net-(D17-A)") (class "Default")
      (node (ref "D17") (pin "2") (pinfunction "A_2") (pintype "passive"))
      (node (ref "IC12") (pin "4") (pinfunction "SENSE_INPUT_4") (pintype "passive"))
      (node (ref "Q23") (pin "3") (pinfunction "S_3") (pintype "passive"))
      (node (ref "R36") (pin "2") (pinfunction "2_2") (pintype "passive"))
    )
    (net (code "32") (name "Net-(D18-A)") (class "Default")
      (node (ref "D18") (pin "2") (pinfunction "A_2") (pintype "passive"))
      (node (ref "IC13") (pin "4") (pinfunction "SENSE_INPUT_4") (pintype "passive"))
      (node (ref "Q24") (pin "3") (pinfunction "S_3") (pintype "passive"))
      (node (ref "R37") (pin "2") (pinfunction "2_2") (pintype "passive"))
    )
    (net (code "33") (name "Net-(D19-A)") (class "Default")
      (node (ref "D19") (pin "2") (pinfunction "A_2") (pintype "passive"))
      (node (ref "J4") (pin "1") (pinfunction "1_1") (pintype "passive"))
    )
    (net (code "34") (name "Net-(D20-A)") (class "Default")
      (node (ref "D20") (pin "2") (pinfunction "A_2") (pintype "passive"))
      (node (ref "J4") (pin "2") (pinfunction "2_2") (pintype "passive"))
    )
    (net (code "35") (name "Net-(D21-A)") (class "Default")
      (node (ref "D21") (pin "2") (pinfunction "A_2") (pintype "passive"))
      (node (ref "J4") (pin "3") (pinfunction "3_3") (pintype "passive"))
    )
    (net (code "36") (name "Net-(D22-A)") (class "Default")
      (node (ref "D22") (pin "2") (pinfunction "A_2") (pintype "passive"))
      (node (ref "J4") (pin "4") (pinfunction "4_4") (pintype "passive"))
    )
    (net (code "37") (name "Net-(D23-A)") (class "Default")
      (node (ref "D23") (pin "2") (pinfunction "A_2") (pintype "passive"))
      (node (ref "J4") (pin "5") (pinfunction "5_5") (pintype "passive"))
    )
    (net (code "38") (name "Net-(D24-A)") (class "Default")
      (node (ref "D24") (pin "2") (pinfunction "A_2") (pintype "passive"))
      (node (ref "J4") (pin "6") (pinfunction "6_6") (pintype "passive"))
    )
    (net (code "39") (name "Net-(IC8-COMP)") (class "Default")
      (node (ref "C42") (pin "2") (pinfunction "2_2") (pintype "passive"))
      (node (ref "IC8") (pin "3") (pinfunction "COMP_3") (pintype "passive"))
    )
    (net (code "40") (name "Net-(IC8-OUT)") (class "Default")
      (node (ref "C42") (pin "1") (pinfunction "1_1") (pintype "passive"))
      (node (ref "IC8") (pin "2") (pinfunction "OUT_2") (pintype "passive"))
      (node (ref "Q13") (pin "2") (pinfunction "B_2") (pintype "passive"))
    )
    (net (code "41") (name "Net-(IC8-TIMER)") (class "Default")
      (node (ref "C33") (pin "1") (pinfunction "1_1") (pintype "passive"))
      (node (ref "IC8") (pin "8") (pinfunction "TIMER_8") (pintype "passive"))
      (node (ref "R23") (pin "2") (pinfunction "2_2") (pintype "passive"))
    )
    (net (code "42") (name "Net-(IC9-COMP)") (class "Default")
      (node (ref "C43") (pin "2") (pinfunction "2_2") (pintype "passive"))
      (node (ref "IC9") (pin "3") (pinfunction "COMP_3") (pintype "passive"))
    )
    (net (code "43") (name "Net-(IC9-OUT)") (class "Default")
      (node (ref "C43") (pin "1") (pinfunction "1_1") (pintype "passive"))
      (node (ref "IC9") (pin "2") (pinfunction "OUT_2") (pintype "passive"))
      (node (ref "Q14") (pin "2") (pinfunction "B_2") (pintype "passive"))
    )
    (net (code "44") (name "Net-(IC9-TIMER)") (class "Default")
      (node (ref "C34") (pin "1") (pinfunction "1_1") (pintype "passive"))
      (node (ref "IC9") (pin "8") (pinfunction "TIMER_8") (pintype "passive"))
      (node (ref "R24") (pin "2") (pinfunction "2_2") (pintype "passive"))
    )
    (net (code "45") (name "Net-(IC10-COMP)") (class "Default")
      (node (ref "C44") (pin "2") (pinfunction "2_2") (pintype "passive"))
      (node (ref "IC10") (pin "3") (pinfunction "COMP_3") (pintype "passive"))
    )
    (net (code "46") (name "Net-(IC10-OUT)") (class "Default")
      (node (ref "C44") (pin "1") (pinfunction "1_1") (pintype "passive"))
      (node (ref "IC10") (pin "2") (pinfunction "OUT_2") (pintype "passive"))
      (node (ref "Q15") (pin "2") (pinfunction "B_2") (pintype "passive"))
    )
    (net (code "47") (name "Net-(IC10-TIMER)") (class "Default")
      (node (ref "C35") (pin "1") (pinfunction "1_1") (pintype "passive"))
      (node (ref "IC10") (pin "8") (pinfunction "TIMER_8") (pintype "passive"))
      (node (ref "R25") (pin "2") (pinfunction "2_2") (pintype "passive"))
    )
    (net (code "48") (name "Net-(IC11-COMP)") (class "Default")
      (node (ref "C54") (pin "2") (pinfunction "2_2") (pintype "passive"))
      (node (ref "IC11") (pin "3") (pinfunction "COMP_3") (pintype "passive"))
    )
    (net (code "49") (name "Net-(IC11-OUT)") (class "Default")
      (node (ref "C54") (pin "1") (pinfunction "1_1") (pintype "passive"))
      (node (ref "IC11") (pin "2") (pinfunction "OUT_2") (pintype "passive"))
      (node (ref "Q19") (pin "2") (pinfunction "B_2") (pintype "passive"))
    )
    (net (code "50") (name "Net-(IC11-TIMER)") (class "Default")
      (node (ref "C45") (pin "1") (pinfunction "1_1") (pintype "passive"))
      (node (ref "IC11") (pin "8") (pinfunction "TIMER_8") (pintype "passive"))
      (node (ref "R32") (pin "2") (pinfunction "2_2") (pintype "passive"))
    )
    (net (code "51") (name "Net-(IC12-COMP)") (class "Default")
      (node (ref "C55") (pin "2") (pinfunction "2_2") (pintype "passive"))
      (node (ref "IC12") (pin "3") (pinfunction "COMP_3") (pintype "passive"))
    )
    (net (code "52") (name "Net-(IC12-OUT)") (class "Default")
      (node (ref "C55") (pin "1") (pinfunction "1_1") (pintype "passive"))
      (node (ref "IC12") (pin "2") (pinfunction "OUT_2") (pintype "passive"))
      (node (ref "Q20") (pin "2") (pinfunction "B_2") (pintype "passive"))
    )
    (net (code "53") (name "Net-(IC12-TIMER)") (class "Default")
      (node (ref "C46") (pin "1") (pinfunction "1_1") (pintype "passive"))
      (node (ref "IC12") (pin "8") (pinfunction "TIMER_8") (pintype "passive"))
      (node (ref "R33") (pin "2") (pinfunction "2_2") (pintype "passive"))
    )
    (net (code "54") (name "Net-(IC13-COMP)") (class "Default")
      (node (ref "C56") (pin "2") (pinfunction "2_2") (pintype "passive"))
      (node (ref "IC13") (pin "3") (pinfunction "COMP_3") (pintype "passive"))
    )
    (net (code "55") (name "Net-(IC13-OUT)") (class "Default")
      (node (ref "C56") (pin "1") (pinfunction "1_1") (pintype "passive"))
      (node (ref "IC13") (pin "2") (pinfunction "OUT_2") (pintype "passive"))
      (node (ref "Q21") (pin "2") (pinfunction "B_2") (pintype "passive"))
    )
    (net (code "56") (name "Net-(IC13-TIMER)") (class "Default")
      (node (ref "C47") (pin "1") (pinfunction "1_1") (pintype "passive"))
      (node (ref "IC13") (pin "8") (pinfunction "TIMER_8") (pintype "passive"))
      (node (ref "R34") (pin "2") (pinfunction "2_2") (pintype "passive"))
    )
    (net (code "57") (name "Net-(LED1-A)") (class "Default")
      (node (ref "LED1") (pin "1") (pinfunction "A_1") (pintype "passive"))
      (node (ref "R38") (pin "1") (pinfunction "1_1") (pintype "passive"))
    )
    (net (code "58") (name "Net-(Q13-E)") (class "Default")
      (node (ref "Q13") (pin "3") (pinfunction "E_3") (pintype "passive"))
      (node (ref "Q16") (pin "1") (pinfunction "G_1") (pintype "passive"))
      (node (ref "R20") (pin "2") (pinfunction "2_2") (pintype "passive"))
    )
    (net (code "59") (name "Net-(Q14-E)") (class "Default")
      (node (ref "Q14") (pin "3") (pinfunction "E_3") (pintype "passive"))
      (node (ref "Q17") (pin "1") (pinfunction "G_1") (pintype "passive"))
      (node (ref "R21") (pin "2") (pinfunction "2_2") (pintype "passive"))
    )
    (net (code "60") (name "Net-(Q15-E)") (class "Default")
      (node (ref "Q15") (pin "3") (pinfunction "E_3") (pintype "passive"))
      (node (ref "Q18") (pin "1") (pinfunction "G_1") (pintype "passive"))
      (node (ref "R22") (pin "2") (pinfunction "2_2") (pintype "passive"))
    )
    (net (code "61") (name "Net-(Q19-E)") (class "Default")
      (node (ref "Q19") (pin "3") (pinfunction "E_3") (pintype "passive"))
      (node (ref "Q22") (pin "1") (pinfunction "G_1") (pintype "passive"))
      (node (ref "R29") (pin "2") (pinfunction "2_2") (pintype "passive"))
    )
    (net (code "62") (name "Net-(Q20-E)") (class "Default")
      (node (ref "Q20") (pin "3") (pinfunction "E_3") (pintype "passive"))
      (node (ref "Q23") (pin "1") (pinfunction "G_1") (pintype "passive"))
      (node (ref "R30") (pin "2") (pinfunction "2_2") (pintype "passive"))
    )
    (net (code "63") (name "Net-(Q21-E)") (class "Default")
      (node (ref "Q21") (pin "3") (pinfunction "E_3") (pintype "passive"))
      (node (ref "Q24") (pin "1") (pinfunction "G_1") (pintype "passive"))
      (node (ref "R31") (pin "2") (pinfunction "2_2") (pintype "passive"))
    )
    (net (code "64") (name "unconnected-(U6-3I0-Pad11)") (class "Default")
      (node (ref "U6") (pin "11") (pinfunction "3I0_11") (pintype "input+no_connect"))
    )
    (net (code "65") (name "unconnected-(U6-3I1-Pad10)") (class "Default")
      (node (ref "U6") (pin "10") (pinfunction "3I1_10") (pintype "input+no_connect"))
    )
    (net (code "66") (name "unconnected-(U6-3Y-Pad9)") (class "Default")
      (node (ref "U6") (pin "9") (pinfunction "3Y_9") (pintype "output+no_connect"))
    )
    (net (code "67") (name "unconnected-(U6-4I0-Pad14)") (class "Default")
      (node (ref "U6") (pin "14") (pinfunction "4I0_14") (pintype "input+no_connect"))
    )
    (net (code "68") (name "unconnected-(U6-4I1-Pad13)") (class "Default")
      (node (ref "U6") (pin "13") (pinfunction "4I1_13") (pintype "input+no_connect"))
    )
    (net (code "69") (name "unconnected-(U6-4Y-Pad12)") (class "Default")
      (node (ref "U6") (pin "12") (pinfunction "4Y_12") (pintype "output+no_connect"))
    )
  )
)
